# Pressure_INPUT.net
KiCad netlist of a schematic drawn in Altium Designer
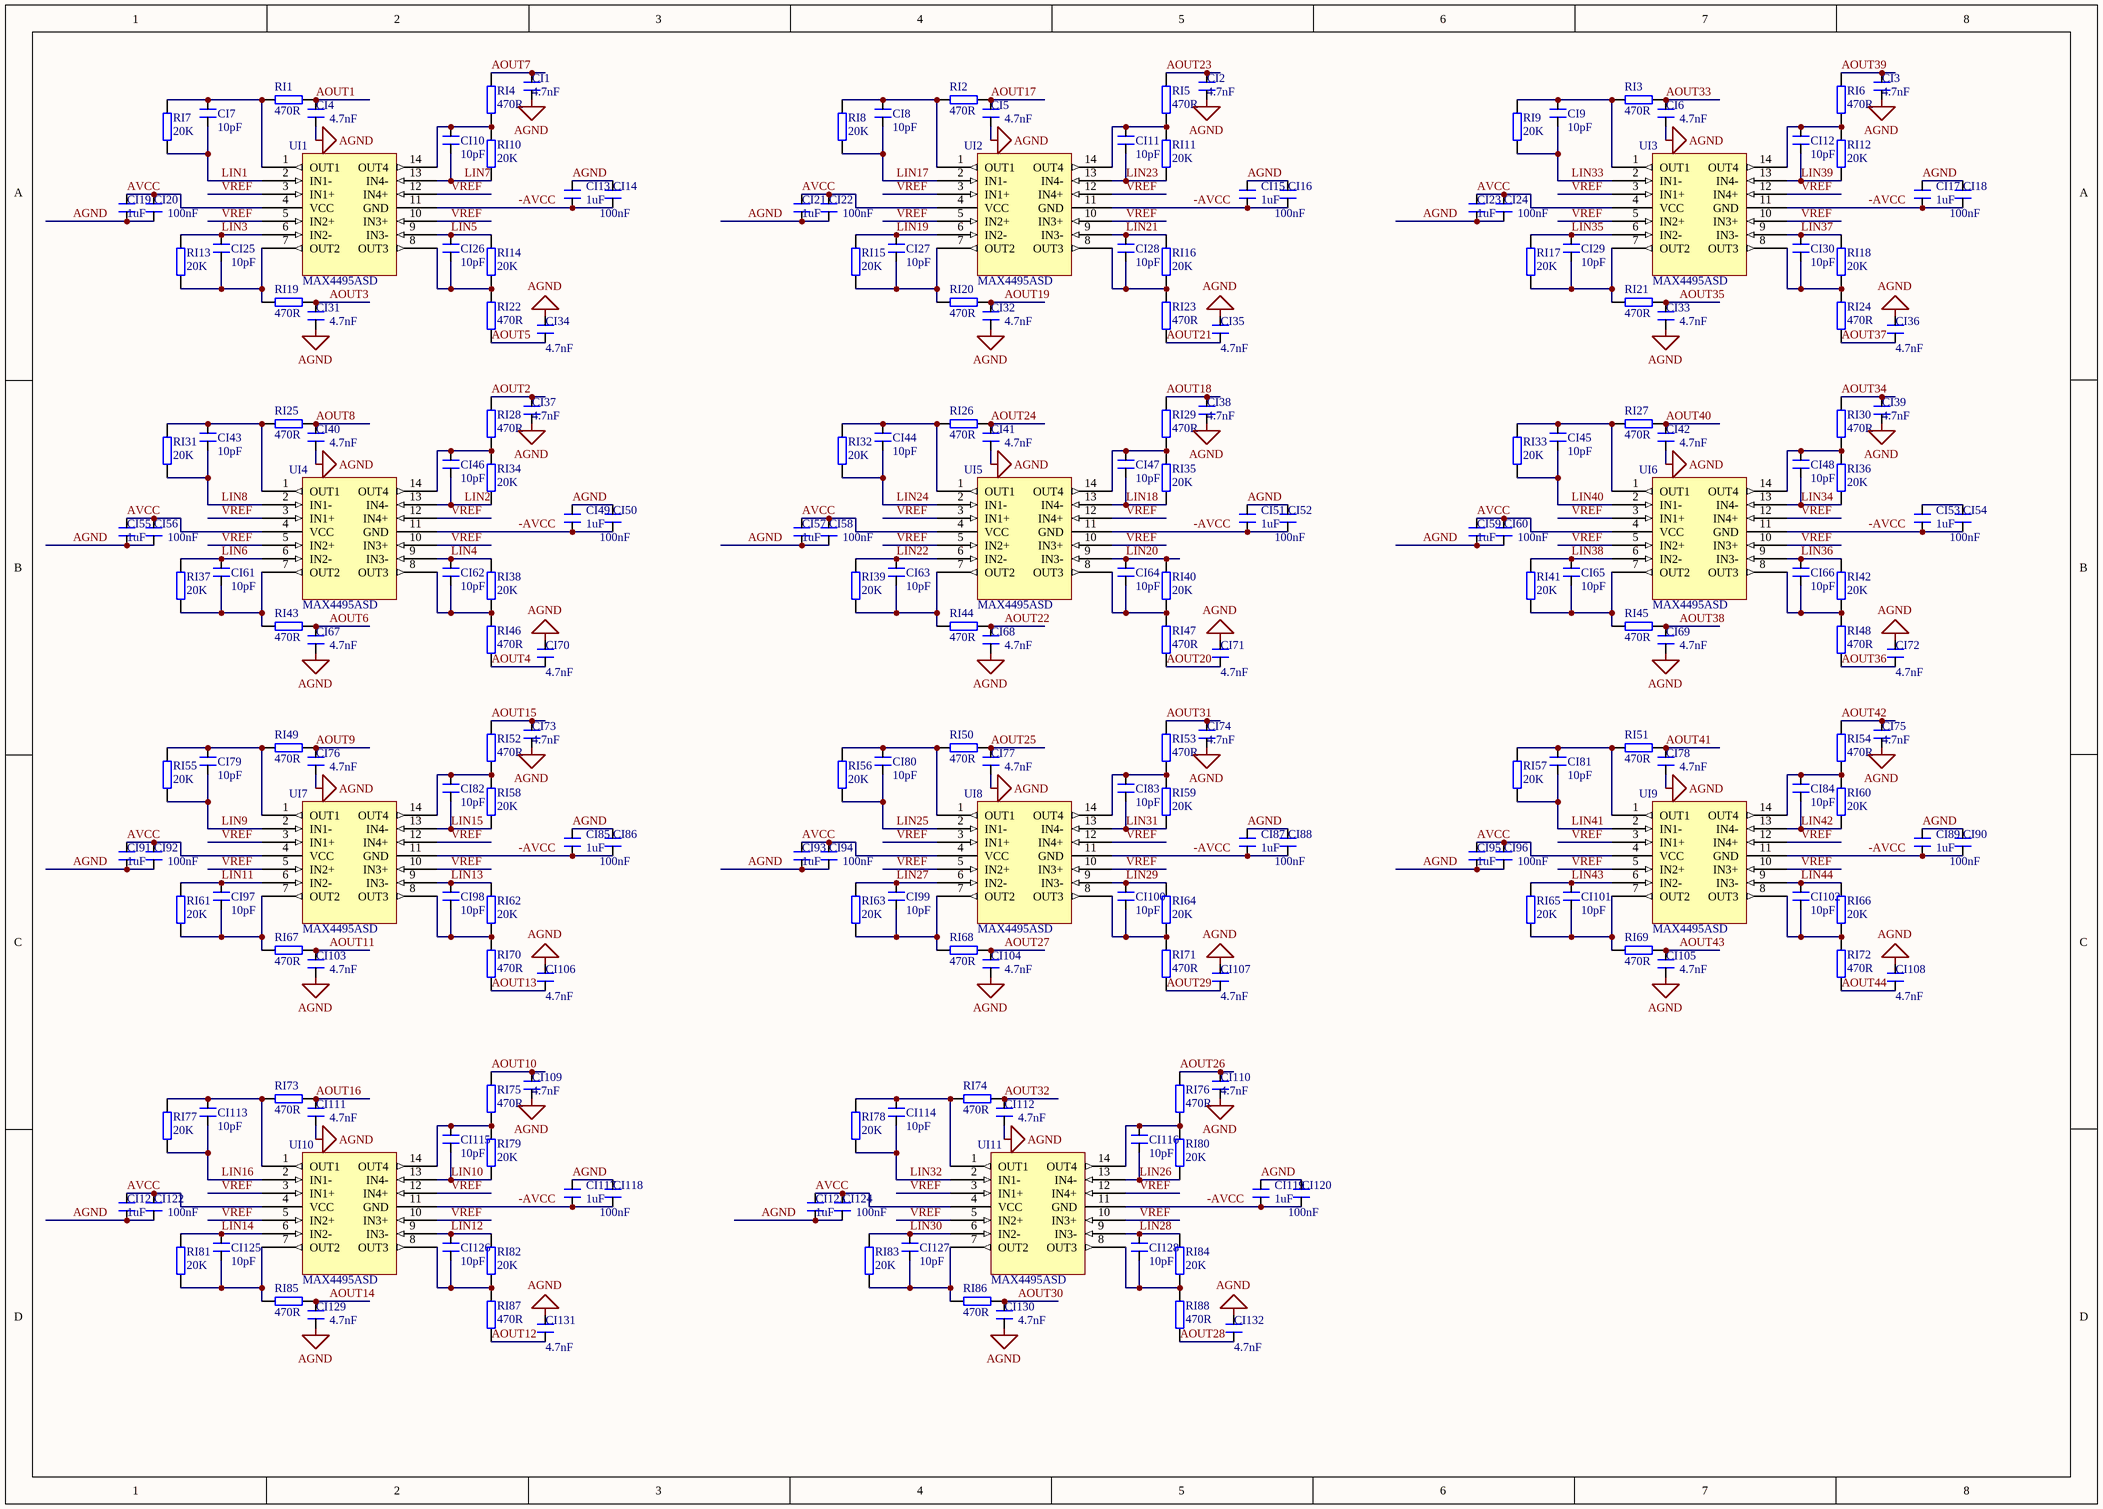
[diagram p0: Pressure_INPUT.SchDoc]

(export (version "E")
  (design (tool "Eeschema 10.0.6"))
  (components
    (comp (ref "CI1") (value "4.7nF") (footprint "C0603_HSC100") (libsource (lib "*") (part "CAP_M")))
    (comp (ref "CI2") (value "4.7nF") (footprint "C0603_HSC100") (libsource (lib "*") (part "CAP_M")))
    (comp (ref "CI3") (value "4.7nF") (footprint "C0603_HSC100") (libsource (lib "*") (part "CAP_M")))
    (comp (ref "CI4") (value "4.7nF") (footprint "C0603_HSC100") (libsource (lib "*") (part "CAP_M")))
    (comp (ref "CI5") (value "4.7nF") (footprint "C0603_HSC100") (libsource (lib "*") (part "CAP_M")))
    (comp (ref "CI6") (value "4.7nF") (footprint "C0603_HSC100") (libsource (lib "*") (part "CAP_M")))
    (comp (ref "CI7") (value "10pF") (footprint "C0603_HSC100") (libsource (lib "*") (part "CAP_M")))
    (comp (ref "CI8") (value "10pF") (footprint "C0603_HSC100") (libsource (lib "*") (part "CAP_M")))
    (comp (ref "CI9") (value "10pF") (footprint "C0603_HSC100") (libsource (lib "*") (part "CAP_M")))
    (comp (ref "CI10") (value "10pF") (footprint "C0603_HSC100") (libsource (lib "*") (part "CAP_M")))
    (comp (ref "CI11") (value "10pF") (footprint "C0603_HSC100") (libsource (lib "*") (part "CAP_M")))
    (comp (ref "CI12") (value "10pF") (footprint "C0603_HSC100") (libsource (lib "*") (part "CAP_M")))
    (comp (ref "CI13") (value "1uF") (footprint "C0603_HSC100") (libsource (lib "*") (part "CAP_M")))
    (comp (ref "CI14") (value "100nF") (footprint "C0603_HSC100") (libsource (lib "*") (part "CAP_M")))
    (comp (ref "CI15") (value "1uF") (footprint "C0603_HSC100") (libsource (lib "*") (part "CAP_M")))
    (comp (ref "CI16") (value "100nF") (footprint "C0603_HSC100") (libsource (lib "*") (part "CAP_M")))
    (comp (ref "CI17") (value "1uF") (footprint "C0603_HSC100") (libsource (lib "*") (part "CAP_M")))
    (comp (ref "CI18") (value "100nF") (footprint "C0603_HSC100") (libsource (lib "*") (part "CAP_M")))
    (comp (ref "CI19") (value "1uF") (footprint "C0603_HSC100") (libsource (lib "*") (part "CAP_M")))
    (comp (ref "CI20") (value "100nF") (footprint "C0603_HSC100") (libsource (lib "*") (part "CAP_M")))
    (comp (ref "CI21") (value "1uF") (footprint "C0603_HSC100") (libsource (lib "*") (part "CAP_M")))
    (comp (ref "CI22") (value "100nF") (footprint "C0603_HSC100") (libsource (lib "*") (part "CAP_M")))
    (comp (ref "CI23") (value "1uF") (footprint "C0603_HSC100") (libsource (lib "*") (part "CAP_M")))
    (comp (ref "CI24") (value "100nF") (footprint "C0603_HSC100") (libsource (lib "*") (part "CAP_M")))
    (comp (ref "CI25") (value "10pF") (footprint "C0603_HSC100") (libsource (lib "*") (part "CAP_M")))
    (comp (ref "CI26") (value "10pF") (footprint "C0603_HSC100") (libsource (lib "*") (part "CAP_M")))
    (comp (ref "CI27") (value "10pF") (footprint "C0603_HSC100") (libsource (lib "*") (part "CAP_M")))
    (comp (ref "CI28") (value "10pF") (footprint "C0603_HSC100") (libsource (lib "*") (part "CAP_M")))
    (comp (ref "CI29") (value "10pF") (footprint "C0603_HSC100") (libsource (lib "*") (part "CAP_M")))
    (comp (ref "CI30") (value "10pF") (footprint "C0603_HSC100") (libsource (lib "*") (part "CAP_M")))
    (comp (ref "CI31") (value "4.7nF") (footprint "C0603_HSC100") (libsource (lib "*") (part "CAP_M")))
    (comp (ref "CI32") (value "4.7nF") (footprint "C0603_HSC100") (libsource (lib "*") (part "CAP_M")))
    (comp (ref "CI33") (value "4.7nF") (footprint "C0603_HSC100") (libsource (lib "*") (part "CAP_M")))
    (comp (ref "CI34") (value "4.7nF") (footprint "C0603_HSC100") (libsource (lib "*") (part "CAP_M")))
    (comp (ref "CI35") (value "4.7nF") (footprint "C0603_HSC100") (libsource (lib "*") (part "CAP_M")))
    (comp (ref "CI36") (value "4.7nF") (footprint "C0603_HSC100") (libsource (lib "*") (part "CAP_M")))
    (comp (ref "CI37") (value "4.7nF") (footprint "C0603_HSC100") (libsource (lib "*") (part "CAP_M")))
    (comp (ref "CI38") (value "4.7nF") (footprint "C0603_HSC100") (libsource (lib "*") (part "CAP_M")))
    (comp (ref "CI39") (value "4.7nF") (footprint "C0603_HSC100") (libsource (lib "*") (part "CAP_M")))
    (comp (ref "CI40") (value "4.7nF") (footprint "C0603_HSC100") (libsource (lib "*") (part "CAP_M")))
    (comp (ref "CI41") (value "4.7nF") (footprint "C0603_HSC100") (libsource (lib "*") (part "CAP_M")))
    (comp (ref "CI42") (value "4.7nF") (footprint "C0603_HSC100") (libsource (lib "*") (part "CAP_M")))
    (comp (ref "CI43") (value "10pF") (footprint "C0603_HSC100") (libsource (lib "*") (part "CAP_M")))
    (comp (ref "CI44") (value "10pF") (footprint "C0603_HSC100") (libsource (lib "*") (part "CAP_M")))
    (comp (ref "CI45") (value "10pF") (footprint "C0603_HSC100") (libsource (lib "*") (part "CAP_M")))
    (comp (ref "CI46") (value "10pF") (footprint "C0603_HSC100") (libsource (lib "*") (part "CAP_M")))
    (comp (ref "CI47") (value "10pF") (footprint "C0603_HSC100") (libsource (lib "*") (part "CAP_M")))
    (comp (ref "CI48") (value "10pF") (footprint "C0603_HSC100") (libsource (lib "*") (part "CAP_M")))
    (comp (ref "CI49") (value "1uF") (footprint "C0603_HSC100") (libsource (lib "*") (part "CAP_M")))
    (comp (ref "CI50") (value "100nF") (footprint "C0603_HSC100") (libsource (lib "*") (part "CAP_M")))
    (comp (ref "CI51") (value "1uF") (footprint "C0603_HSC100") (libsource (lib "*") (part "CAP_M")))
    (comp (ref "CI52") (value "100nF") (footprint "C0603_HSC100") (libsource (lib "*") (part "CAP_M")))
    (comp (ref "CI53") (value "1uF") (footprint "C0603_HSC100") (libsource (lib "*") (part "CAP_M")))
    (comp (ref "CI54") (value "100nF") (footprint "C0603_HSC100") (libsource (lib "*") (part "CAP_M")))
    (comp (ref "CI55") (value "1uF") (footprint "C0603_HSC100") (libsource (lib "*") (part "CAP_M")))
    (comp (ref "CI56") (value "100nF") (footprint "C0603_HSC100") (libsource (lib "*") (part "CAP_M")))
    (comp (ref "CI57") (value "1uF") (footprint "C0603_HSC100") (libsource (lib "*") (part "CAP_M")))
    (comp (ref "CI58") (value "100nF") (footprint "C0603_HSC100") (libsource (lib "*") (part "CAP_M")))
    (comp (ref "CI59") (value "1uF") (footprint "C0603_HSC100") (libsource (lib "*") (part "CAP_M")))
    (comp (ref "CI60") (value "100nF") (footprint "C0603_HSC100") (libsource (lib "*") (part "CAP_M")))
    (comp (ref "CI61") (value "10pF") (footprint "C0603_HSC100") (libsource (lib "*") (part "CAP_M")))
    (comp (ref "CI62") (value "10pF") (footprint "C0603_HSC100") (libsource (lib "*") (part "CAP_M")))
    (comp (ref "CI63") (value "10pF") (footprint "C0603_HSC100") (libsource (lib "*") (part "CAP_M")))
    (comp (ref "CI64") (value "10pF") (footprint "C0603_HSC100") (libsource (lib "*") (part "CAP_M")))
    (comp (ref "CI65") (value "10pF") (footprint "C0603_HSC100") (libsource (lib "*") (part "CAP_M")))
    (comp (ref "CI66") (value "10pF") (footprint "C0603_HSC100") (libsource (lib "*") (part "CAP_M")))
    (comp (ref "CI67") (value "4.7nF") (footprint "C0603_HSC100") (libsource (lib "*") (part "CAP_M")))
    (comp (ref "CI68") (value "4.7nF") (footprint "C0603_HSC100") (libsource (lib "*") (part "CAP_M")))
    (comp (ref "CI69") (value "4.7nF") (footprint "C0603_HSC100") (libsource (lib "*") (part "CAP_M")))
    (comp (ref "CI70") (value "4.7nF") (footprint "C0603_HSC100") (libsource (lib "*") (part "CAP_M")))
    (comp (ref "CI71") (value "4.7nF") (footprint "C0603_HSC100") (libsource (lib "*") (part "CAP_M")))
    (comp (ref "CI72") (value "4.7nF") (footprint "C0603_HSC100") (libsource (lib "*") (part "CAP_M")))
    (comp (ref "CI73") (value "4.7nF") (footprint "C0603_HSC100") (libsource (lib "*") (part "CAP_M")))
    (comp (ref "CI74") (value "4.7nF") (footprint "C0603_HSC100") (libsource (lib "*") (part "CAP_M")))
    (comp (ref "CI75") (value "4.7nF") (footprint "C0603_HSC100") (libsource (lib "*") (part "CAP_M")))
    (comp (ref "CI76") (value "4.7nF") (footprint "C0603_HSC100") (libsource (lib "*") (part "CAP_M")))
    (comp (ref "CI77") (value "4.7nF") (footprint "C0603_HSC100") (libsource (lib "*") (part "CAP_M")))
    (comp (ref "CI78") (value "4.7nF") (footprint "C0603_HSC100") (libsource (lib "*") (part "CAP_M")))
    (comp (ref "CI79") (value "10pF") (footprint "C0603_HSC100") (libsource (lib "*") (part "CAP_M")))
    (comp (ref "CI80") (value "10pF") (footprint "C0603_HSC100") (libsource (lib "*") (part "CAP_M")))
    (comp (ref "CI81") (value "10pF") (footprint "C0603_HSC100") (libsource (lib "*") (part "CAP_M")))
    (comp (ref "CI82") (value "10pF") (footprint "C0603_HSC100") (libsource (lib "*") (part "CAP_M")))
    (comp (ref "CI83") (value "10pF") (footprint "C0603_HSC100") (libsource (lib "*") (part "CAP_M")))
    (comp (ref "CI84") (value "10pF") (footprint "C0603_HSC100") (libsource (lib "*") (part "CAP_M")))
    (comp (ref "CI85") (value "1uF") (footprint "C0603_HSC100") (libsource (lib "*") (part "CAP_M")))
    (comp (ref "CI86") (value "100nF") (footprint "C0603_HSC100") (libsource (lib "*") (part "CAP_M")))
    (comp (ref "CI87") (value "1uF") (footprint "C0603_HSC100") (libsource (lib "*") (part "CAP_M")))
    (comp (ref "CI88") (value "100nF") (footprint "C0603_HSC100") (libsource (lib "*") (part "CAP_M")))
    (comp (ref "CI89") (value "1uF") (footprint "C0603_HSC100") (libsource (lib "*") (part "CAP_M")))
    (comp (ref "CI90") (value "100nF") (footprint "C0603_HSC100") (libsource (lib "*") (part "CAP_M")))
    (comp (ref "CI91") (value "1uF") (footprint "C0603_HSC100") (libsource (lib "*") (part "CAP_M")))
    (comp (ref "CI92") (value "100nF") (footprint "C0603_HSC100") (libsource (lib "*") (part "CAP_M")))
    (comp (ref "CI93") (value "1uF") (footprint "C0603_HSC100") (libsource (lib "*") (part "CAP_M")))
    (comp (ref "CI94") (value "100nF") (footprint "C0603_HSC100") (libsource (lib "*") (part "CAP_M")))
    (comp (ref "CI95") (value "1uF") (footprint "C0603_HSC100") (libsource (lib "*") (part "CAP_M")))
    (comp (ref "CI96") (value "100nF") (footprint "C0603_HSC100") (libsource (lib "*") (part "CAP_M")))
    (comp (ref "CI97") (value "10pF") (footprint "C0603_HSC100") (libsource (lib "*") (part "CAP_M")))
    (comp (ref "CI98") (value "10pF") (footprint "C0603_HSC100") (libsource (lib "*") (part "CAP_M")))
    (comp (ref "CI99") (value "10pF") (footprint "C0603_HSC100") (libsource (lib "*") (part "CAP_M")))
    (comp (ref "CI100") (value "10pF") (footprint "C0603_HSC100") (libsource (lib "*") (part "CAP_M")))
    (comp (ref "CI101") (value "10pF") (footprint "C0603_HSC100") (libsource (lib "*") (part "CAP_M")))
    (comp (ref "CI102") (value "10pF") (footprint "C0603_HSC100") (libsource (lib "*") (part "CAP_M")))
    (comp (ref "CI103") (value "4.7nF") (footprint "C0603_HSC100") (libsource (lib "*") (part "CAP_M")))
    (comp (ref "CI104") (value "4.7nF") (footprint "C0603_HSC100") (libsource (lib "*") (part "CAP_M")))
    (comp (ref "CI105") (value "4.7nF") (footprint "C0603_HSC100") (libsource (lib "*") (part "CAP_M")))
    (comp (ref "CI106") (value "4.7nF") (footprint "C0603_HSC100") (libsource (lib "*") (part "CAP_M")))
    (comp (ref "CI107") (value "4.7nF") (footprint "C0603_HSC100") (libsource (lib "*") (part "CAP_M")))
    (comp (ref "CI108") (value "4.7nF") (footprint "C0603_HSC100") (libsource (lib "*") (part "CAP_M")))
    (comp (ref "CI109") (value "4.7nF") (footprint "C0603_HSC100") (libsource (lib "*") (part "CAP_M")))
    (comp (ref "CI110") (value "4.7nF") (footprint "C0603_HSC100") (libsource (lib "*") (part "CAP_M")))
    (comp (ref "CI111") (value "4.7nF") (footprint "C0603_HSC100") (libsource (lib "*") (part "CAP_M")))
    (comp (ref "CI112") (value "4.7nF") (footprint "C0603_HSC100") (libsource (lib "*") (part "CAP_M")))
    (comp (ref "CI113") (value "10pF") (footprint "C0603_HSC100") (libsource (lib "*") (part "CAP_M")))
    (comp (ref "CI114") (value "10pF") (footprint "C0603_HSC100") (libsource (lib "*") (part "CAP_M")))
    (comp (ref "CI115") (value "10pF") (footprint "C0603_HSC100") (libsource (lib "*") (part "CAP_M")))
    (comp (ref "CI116") (value "10pF") (footprint "C0603_HSC100") (libsource (lib "*") (part "CAP_M")))
    (comp (ref "CI117") (value "1uF") (footprint "C0603_HSC100") (libsource (lib "*") (part "CAP_M")))
    (comp (ref "CI118") (value "100nF") (footprint "C0603_HSC100") (libsource (lib "*") (part "CAP_M")))
    (comp (ref "CI119") (value "1uF") (footprint "C0603_HSC100") (libsource (lib "*") (part "CAP_M")))
    (comp (ref "CI120") (value "100nF") (footprint "C0603_HSC100") (libsource (lib "*") (part "CAP_M")))
    (comp (ref "CI121") (value "1uF") (footprint "C0603_HSC100") (libsource (lib "*") (part "CAP_M")))
    (comp (ref "CI122") (value "100nF") (footprint "C0603_HSC100") (libsource (lib "*") (part "CAP_M")))
    (comp (ref "CI123") (value "1uF") (footprint "C0603_HSC100") (libsource (lib "*") (part "CAP_M")))
    (comp (ref "CI124") (value "100nF") (footprint "C0603_HSC100") (libsource (lib "*") (part "CAP_M")))
    (comp (ref "CI125") (value "10pF") (footprint "C0603_HSC100") (libsource (lib "*") (part "CAP_M")))
    (comp (ref "CI126") (value "10pF") (footprint "C0603_HSC100") (libsource (lib "*") (part "CAP_M")))
    (comp (ref "CI127") (value "10pF") (footprint "C0603_HSC100") (libsource (lib "*") (part "CAP_M")))
    (comp (ref "CI128") (value "10pF") (footprint "C0603_HSC100") (libsource (lib "*") (part "CAP_M")))
    (comp (ref "CI129") (value "4.7nF") (footprint "C0603_HSC100") (libsource (lib "*") (part "CAP_M")))
    (comp (ref "CI130") (value "4.7nF") (footprint "C0603_HSC100") (libsource (lib "*") (part "CAP_M")))
    (comp (ref "CI131") (value "4.7nF") (footprint "C0603_HSC100") (libsource (lib "*") (part "CAP_M")))
    (comp (ref "CI132") (value "4.7nF") (footprint "C0603_HSC100") (libsource (lib "*") (part "CAP_M")))
    (comp (ref "RI1") (value "470R") (footprint "R0603_HSC100") (libsource (lib "*") (part "RES")))
    (comp (ref "RI2") (value "470R") (footprint "R0603_HSC100") (libsource (lib "*") (part "RES")))
    (comp (ref "RI3") (value "470R") (footprint "R0603_HSC100") (libsource (lib "*") (part "RES")))
    (comp (ref "RI4") (value "470R") (footprint "R0603_HSC100") (libsource (lib "*") (part "RES")))
    (comp (ref "RI5") (value "470R") (footprint "R0603_HSC100") (libsource (lib "*") (part "RES")))
    (comp (ref "RI6") (value "470R") (footprint "R0603_HSC100") (libsource (lib "*") (part "RES")))
    (comp (ref "RI7") (value "20K") (footprint "R0603_HSC100") (libsource (lib "*") (part "RES")))
    (comp (ref "RI8") (value "20K") (footprint "R0603_HSC100") (libsource (lib "*") (part "RES")))
    (comp (ref "RI9") (value "20K") (footprint "R0603_HSC100") (libsource (lib "*") (part "RES")))
    (comp (ref "RI10") (value "20K") (footprint "R0603_HSC100") (libsource (lib "*") (part "RES")))
    (comp (ref "RI11") (value "20K") (footprint "R0603_HSC100") (libsource (lib "*") (part "RES")))
    (comp (ref "RI12") (value "20K") (footprint "R0603_HSC100") (libsource (lib "*") (part "RES")))
    (comp (ref "RI13") (value "20K") (footprint "R0603_HSC100") (libsource (lib "*") (part "RES")))
    (comp (ref "RI14") (value "20K") (footprint "R0603_HSC100") (libsource (lib "*") (part "RES")))
    (comp (ref "RI15") (value "20K") (footprint "R0603_HSC100") (libsource (lib "*") (part "RES")))
    (comp (ref "RI16") (value "20K") (footprint "R0603_HSC100") (libsource (lib "*") (part "RES")))
    (comp (ref "RI17") (value "20K") (footprint "R0603_HSC100") (libsource (lib "*") (part "RES")))
    (comp (ref "RI18") (value "20K") (footprint "R0603_HSC100") (libsource (lib "*") (part "RES")))
    (comp (ref "RI19") (value "470R") (footprint "R0603_HSC100") (libsource (lib "*") (part "RES")))
    (comp (ref "RI20") (value "470R") (footprint "R0603_HSC100") (libsource (lib "*") (part "RES")))
    (comp (ref "RI21") (value "470R") (footprint "R0603_HSC100") (libsource (lib "*") (part "RES")))
    (comp (ref "RI22") (value "470R") (footprint "R0603_HSC100") (libsource (lib "*") (part "RES")))
    (comp (ref "RI23") (value "470R") (footprint "R0603_HSC100") (libsource (lib "*") (part "RES")))
    (comp (ref "RI24") (value "470R") (footprint "R0603_HSC100") (libsource (lib "*") (part "RES")))
    (comp (ref "RI25") (value "470R") (footprint "R0603_HSC100") (libsource (lib "*") (part "RES")))
    (comp (ref "RI26") (value "470R") (footprint "R0603_HSC100") (libsource (lib "*") (part "RES")))
    (comp (ref "RI27") (value "470R") (footprint "R0603_HSC100") (libsource (lib "*") (part "RES")))
    (comp (ref "RI28") (value "470R") (footprint "R0603_HSC100") (libsource (lib "*") (part "RES")))
    (comp (ref "RI29") (value "470R") (footprint "R0603_HSC100") (libsource (lib "*") (part "RES")))
    (comp (ref "RI30") (value "470R") (footprint "R0603_HSC100") (libsource (lib "*") (part "RES")))
    (comp (ref "RI31") (value "20K") (footprint "R0603_HSC100") (libsource (lib "*") (part "RES")))
    (comp (ref "RI32") (value "20K") (footprint "R0603_HSC100") (libsource (lib "*") (part "RES")))
    (comp (ref "RI33") (value "20K") (footprint "R0603_HSC100") (libsource (lib "*") (part "RES")))
    (comp (ref "RI34") (value "20K") (footprint "R0603_HSC100") (libsource (lib "*") (part "RES")))
    (comp (ref "RI35") (value "20K") (footprint "R0603_HSC100") (libsource (lib "*") (part "RES")))
    (comp (ref "RI36") (value "20K") (footprint "R0603_HSC100") (libsource (lib "*") (part "RES")))
    (comp (ref "RI37") (value "20K") (footprint "R0603_HSC100") (libsource (lib "*") (part "RES")))
    (comp (ref "RI38") (value "20K") (footprint "R0603_HSC100") (libsource (lib "*") (part "RES")))
    (comp (ref "RI39") (value "20K") (footprint "R0603_HSC100") (libsource (lib "*") (part "RES")))
    (comp (ref "RI40") (value "20K") (footprint "R0603_HSC100") (libsource (lib "*") (part "RES")))
    (comp (ref "RI41") (value "20K") (footprint "R0603_HSC100") (libsource (lib "*") (part "RES")))
    (comp (ref "RI42") (value "20K") (footprint "R0603_HSC100") (libsource (lib "*") (part "RES")))
    (comp (ref "RI43") (value "470R") (footprint "R0603_HSC100") (libsource (lib "*") (part "RES")))
    (comp (ref "RI44") (value "470R") (footprint "R0603_HSC100") (libsource (lib "*") (part "RES")))
    (comp (ref "RI45") (value "470R") (footprint "R0603_HSC100") (libsource (lib "*") (part "RES")))
    (comp (ref "RI46") (value "470R") (footprint "R0603_HSC100") (libsource (lib "*") (part "RES")))
    (comp (ref "RI47") (value "470R") (footprint "R0603_HSC100") (libsource (lib "*") (part "RES")))
    (comp (ref "RI48") (value "470R") (footprint "R0603_HSC100") (libsource (lib "*") (part "RES")))
    (comp (ref "RI49") (value "470R") (footprint "R0603_HSC100") (libsource (lib "*") (part "RES")))
    (comp (ref "RI50") (value "470R") (footprint "R0603_HSC100") (libsource (lib "*") (part "RES")))
    (comp (ref "RI51") (value "470R") (footprint "R0603_HSC100") (libsource (lib "*") (part "RES")))
    (comp (ref "RI52") (value "470R") (footprint "R0603_HSC100") (libsource (lib "*") (part "RES")))
    (comp (ref "RI53") (value "470R") (footprint "R0603_HSC100") (libsource (lib "*") (part "RES")))
    (comp (ref "RI54") (value "470R") (footprint "R0603_HSC100") (libsource (lib "*") (part "RES")))
    (comp (ref "RI55") (value "20K") (footprint "R0603_HSC100") (libsource (lib "*") (part "RES")))
    (comp (ref "RI56") (value "20K") (footprint "R0603_HSC100") (libsource (lib "*") (part "RES")))
    (comp (ref "RI57") (value "20K") (footprint "R0603_HSC100") (libsource (lib "*") (part "RES")))
    (comp (ref "RI58") (value "20K") (footprint "R0603_HSC100") (libsource (lib "*") (part "RES")))
    (comp (ref "RI59") (value "20K") (footprint "R0603_HSC100") (libsource (lib "*") (part "RES")))
    (comp (ref "RI60") (value "20K") (footprint "R0603_HSC100") (libsource (lib "*") (part "RES")))
    (comp (ref "RI61") (value "20K") (footprint "R0603_HSC100") (libsource (lib "*") (part "RES")))
    (comp (ref "RI62") (value "20K") (footprint "R0603_HSC100") (libsource (lib "*") (part "RES")))
    (comp (ref "RI63") (value "20K") (footprint "R0603_HSC100") (libsource (lib "*") (part "RES")))
    (comp (ref "RI64") (value "20K") (footprint "R0603_HSC100") (libsource (lib "*") (part "RES")))
    (comp (ref "RI65") (value "20K") (footprint "R0603_HSC100") (libsource (lib "*") (part "RES")))
    (comp (ref "RI66") (value "20K") (footprint "R0603_HSC100") (libsource (lib "*") (part "RES")))
    (comp (ref "RI67") (value "470R") (footprint "R0603_HSC100") (libsource (lib "*") (part "RES")))
    (comp (ref "RI68") (value "470R") (footprint "R0603_HSC100") (libsource (lib "*") (part "RES")))
    (comp (ref "RI69") (value "470R") (footprint "R0603_HSC100") (libsource (lib "*") (part "RES")))
    (comp (ref "RI70") (value "470R") (footprint "R0603_HSC100") (libsource (lib "*") (part "RES")))
    (comp (ref "RI71") (value "470R") (footprint "R0603_HSC100") (libsource (lib "*") (part "RES")))
    (comp (ref "RI72") (value "470R") (footprint "R0603_HSC100") (libsource (lib "*") (part "RES")))
    (comp (ref "RI73") (value "470R") (footprint "R0603_HSC100") (libsource (lib "*") (part "RES")))
    (comp (ref "RI74") (value "470R") (footprint "R0603_HSC100") (libsource (lib "*") (part "RES")))
    (comp (ref "RI75") (value "470R") (footprint "R0603_HSC100") (libsource (lib "*") (part "RES")))
    (comp (ref "RI76") (value "470R") (footprint "R0603_HSC100") (libsource (lib "*") (part "RES")))
    (comp (ref "RI77") (value "20K") (footprint "R0603_HSC100") (libsource (lib "*") (part "RES")))
    (comp (ref "RI78") (value "20K") (footprint "R0603_HSC100") (libsource (lib "*") (part "RES")))
    (comp (ref "RI79") (value "20K") (footprint "R0603_HSC100") (libsource (lib "*") (part "RES")))
    (comp (ref "RI80") (value "20K") (footprint "R0603_HSC100") (libsource (lib "*") (part "RES")))
    (comp (ref "RI81") (value "20K") (footprint "R0603_HSC100") (libsource (lib "*") (part "RES")))
    (comp (ref "RI82") (value "20K") (footprint "R0603_HSC100") (libsource (lib "*") (part "RES")))
    (comp (ref "RI83") (value "20K") (footprint "R0603_HSC100") (libsource (lib "*") (part "RES")))
    (comp (ref "RI84") (value "20K") (footprint "R0603_HSC100") (libsource (lib "*") (part "RES")))
    (comp (ref "RI85") (value "470R") (footprint "R0603_HSC100") (libsource (lib "*") (part "RES")))
    (comp (ref "RI86") (value "470R") (footprint "R0603_HSC100") (libsource (lib "*") (part "RES")))
    (comp (ref "RI87") (value "470R") (footprint "R0603_HSC100") (libsource (lib "*") (part "RES")))
    (comp (ref "RI88") (value "470R") (footprint "R0603_HSC100") (libsource (lib "*") (part "RES")))
    (comp (ref "UI1") (value "MAX4495ASD") (footprint "SO-14") (libsource (lib "MY_SCH") (part "LM324")))
    (comp (ref "UI2") (value "MAX4495ASD") (footprint "SO-14") (libsource (lib "MY_SCH") (part "LM324")))
    (comp (ref "UI3") (value "MAX4495ASD") (footprint "SO-14") (libsource (lib "MY_SCH") (part "LM324")))
    (comp (ref "UI4") (value "MAX4495ASD") (footprint "SO-14") (libsource (lib "MY_SCH") (part "LM324")))
    (comp (ref "UI5") (value "MAX4495ASD") (footprint "SO-14") (libsource (lib "MY_SCH") (part "LM324")))
    (comp (ref "UI6") (value "MAX4495ASD") (footprint "SO-14") (libsource (lib "MY_SCH") (part "LM324")))
    (comp (ref "UI7") (value "MAX4495ASD") (footprint "SO-14") (libsource (lib "MY_SCH") (part "LM324")))
    (comp (ref "UI8") (value "MAX4495ASD") (footprint "SO-14") (libsource (lib "MY_SCH") (part "LM324")))
    (comp (ref "UI9") (value "MAX4495ASD") (footprint "SO-14") (libsource (lib "MY_SCH") (part "LM324")))
    (comp (ref "UI10") (value "MAX4495ASD") (footprint "SO-14") (libsource (lib "MY_SCH") (part "LM324")))
    (comp (ref "UI11") (value "MAX4495ASD") (footprint "SO-14") (libsource (lib "MY_SCH") (part "LM324")))
  )
  (nets
    (net (code "1") (name "/-AVCC") (class "Default")
      (node (ref "CI117") (pin "2") (pintype "passive"))
      (node (ref "CI118") (pin "2") (pintype "passive"))
      (node (ref "CI119") (pin "2") (pintype "passive"))
      (node (ref "CI120") (pin "2") (pintype "passive"))
      (node (ref "CI13") (pin "2") (pintype "passive"))
      (node (ref "CI14") (pin "2") (pintype "passive"))
      (node (ref "CI15") (pin "2") (pintype "passive"))
      (node (ref "CI16") (pin "2") (pintype "passive"))
      (node (ref "CI17") (pin "2") (pintype "passive"))
      (node (ref "CI18") (pin "2") (pintype "passive"))
      (node (ref "CI49") (pin "2") (pintype "passive"))
      (node (ref "CI50") (pin "2") (pintype "passive"))
      (node (ref "CI51") (pin "2") (pintype "passive"))
      (node (ref "CI52") (pin "2") (pintype "passive"))
      (node (ref "CI53") (pin "2") (pintype "passive"))
      (node (ref "CI54") (pin "2") (pintype "passive"))
      (node (ref "CI85") (pin "2") (pintype "passive"))
      (node (ref "CI86") (pin "2") (pintype "passive"))
      (node (ref "CI87") (pin "2") (pintype "passive"))
      (node (ref "CI88") (pin "2") (pintype "passive"))
      (node (ref "CI89") (pin "2") (pintype "passive"))
      (node (ref "CI90") (pin "2") (pintype "passive"))
      (node (ref "UI1") (pin "11") (pinfunction "GND_11") (pintype "power_in"))
      (node (ref "UI10") (pin "11") (pinfunction "GND_11") (pintype "power_in"))
      (node (ref "UI11") (pin "11") (pinfunction "GND_11") (pintype "power_in"))
      (node (ref "UI2") (pin "11") (pinfunction "GND_11") (pintype "power_in"))
      (node (ref "UI3") (pin "11") (pinfunction "GND_11") (pintype "power_in"))
      (node (ref "UI4") (pin "11") (pinfunction "GND_11") (pintype "power_in"))
      (node (ref "UI5") (pin "11") (pinfunction "GND_11") (pintype "power_in"))
      (node (ref "UI6") (pin "11") (pinfunction "GND_11") (pintype "power_in"))
      (node (ref "UI7") (pin "11") (pinfunction "GND_11") (pintype "power_in"))
      (node (ref "UI8") (pin "11") (pinfunction "GND_11") (pintype "power_in"))
      (node (ref "UI9") (pin "11") (pinfunction "GND_11") (pintype "power_in"))
    )
    (net (code "2") (name "/AOUT1") (class "Default")
      (node (ref "CI4") (pin "1") (pintype "passive"))
      (node (ref "RI1") (pin "1") (pintype "passive"))
    )
    (net (code "3") (name "/AOUT2") (class "Default")
      (node (ref "CI37") (pin "1") (pintype "passive"))
      (node (ref "RI28") (pin "2") (pintype "passive"))
    )
    (net (code "4") (name "/AOUT3") (class "Default")
      (node (ref "CI31") (pin "1") (pintype "passive"))
      (node (ref "RI19") (pin "1") (pintype "passive"))
    )
    (net (code "5") (name "/AOUT4") (class "Default")
      (node (ref "CI70") (pin "2") (pintype "passive"))
      (node (ref "RI46") (pin "2") (pintype "passive"))
    )
    (net (code "6") (name "/AOUT5") (class "Default")
      (node (ref "CI34") (pin "2") (pintype "passive"))
      (node (ref "RI22") (pin "2") (pintype "passive"))
    )
    (net (code "7") (name "/AOUT6") (class "Default")
      (node (ref "CI67") (pin "1") (pintype "passive"))
      (node (ref "RI43") (pin "1") (pintype "passive"))
    )
    (net (code "8") (name "/AOUT7") (class "Default")
      (node (ref "CI1") (pin "1") (pintype "passive"))
      (node (ref "RI4") (pin "2") (pintype "passive"))
    )
    (net (code "9") (name "/AOUT8") (class "Default")
      (node (ref "CI40") (pin "1") (pintype "passive"))
      (node (ref "RI25") (pin "1") (pintype "passive"))
    )
    (net (code "10") (name "/AOUT9") (class "Default")
      (node (ref "CI76") (pin "1") (pintype "passive"))
      (node (ref "RI49") (pin "1") (pintype "passive"))
    )
    (net (code "11") (name "/AOUT10") (class "Default")
      (node (ref "CI109") (pin "1") (pintype "passive"))
      (node (ref "RI75") (pin "2") (pintype "passive"))
    )
    (net (code "12") (name "/AOUT11") (class "Default")
      (node (ref "CI103") (pin "1") (pintype "passive"))
      (node (ref "RI67") (pin "1") (pintype "passive"))
    )
    (net (code "13") (name "/AOUT12") (class "Default")
      (node (ref "CI131") (pin "2") (pintype "passive"))
      (node (ref "RI87") (pin "2") (pintype "passive"))
    )
    (net (code "14") (name "/AOUT13") (class "Default")
      (node (ref "CI106") (pin "2") (pintype "passive"))
      (node (ref "RI70") (pin "2") (pintype "passive"))
    )
    (net (code "15") (name "/AOUT14") (class "Default")
      (node (ref "CI129") (pin "1") (pintype "passive"))
      (node (ref "RI85") (pin "1") (pintype "passive"))
    )
    (net (code "16") (name "/AOUT15") (class "Default")
      (node (ref "CI73") (pin "1") (pintype "passive"))
      (node (ref "RI52") (pin "2") (pintype "passive"))
    )
    (net (code "17") (name "/AOUT16") (class "Default")
      (node (ref "CI111") (pin "1") (pintype "passive"))
      (node (ref "RI73") (pin "1") (pintype "passive"))
    )
    (net (code "18") (name "/AOUT17") (class "Default")
      (node (ref "CI5") (pin "1") (pintype "passive"))
      (node (ref "RI2") (pin "1") (pintype "passive"))
    )
    (net (code "19") (name "/AOUT18") (class "Default")
      (node (ref "CI38") (pin "1") (pintype "passive"))
      (node (ref "RI29") (pin "2") (pintype "passive"))
    )
    (net (code "20") (name "/AOUT19") (class "Default")
      (node (ref "CI32") (pin "1") (pintype "passive"))
      (node (ref "RI20") (pin "1") (pintype "passive"))
    )
    (net (code "21") (name "/AOUT20") (class "Default")
      (node (ref "CI71") (pin "2") (pintype "passive"))
      (node (ref "RI47") (pin "2") (pintype "passive"))
    )
    (net (code "22") (name "/AOUT21") (class "Default")
      (node (ref "CI35") (pin "2") (pintype "passive"))
      (node (ref "RI23") (pin "2") (pintype "passive"))
    )
    (net (code "23") (name "/AOUT22") (class "Default")
      (node (ref "CI68") (pin "1") (pintype "passive"))
      (node (ref "RI44") (pin "1") (pintype "passive"))
    )
    (net (code "24") (name "/AOUT23") (class "Default")
      (node (ref "CI2") (pin "1") (pintype "passive"))
      (node (ref "RI5") (pin "2") (pintype "passive"))
    )
    (net (code "25") (name "/AOUT24") (class "Default")
      (node (ref "CI41") (pin "1") (pintype "passive"))
      (node (ref "RI26") (pin "1") (pintype "passive"))
    )
    (net (code "26") (name "/AOUT25") (class "Default")
      (node (ref "CI77") (pin "1") (pintype "passive"))
      (node (ref "RI50") (pin "1") (pintype "passive"))
    )
    (net (code "27") (name "/AOUT26") (class "Default")
      (node (ref "CI110") (pin "1") (pintype "passive"))
      (node (ref "RI76") (pin "2") (pintype "passive"))
    )
    (net (code "28") (name "/AOUT27") (class "Default")
      (node (ref "CI104") (pin "1") (pintype "passive"))
      (node (ref "RI68") (pin "1") (pintype "passive"))
    )
    (net (code "29") (name "/AOUT28") (class "Default")
      (node (ref "CI132") (pin "2") (pintype "passive"))
      (node (ref "RI88") (pin "2") (pintype "passive"))
    )
    (net (code "30") (name "/AOUT29") (class "Default")
      (node (ref "CI107") (pin "2") (pintype "passive"))
      (node (ref "RI71") (pin "2") (pintype "passive"))
    )
    (net (code "31") (name "/AOUT30") (class "Default")
      (node (ref "CI130") (pin "1") (pintype "passive"))
      (node (ref "RI86") (pin "1") (pintype "passive"))
    )
    (net (code "32") (name "/AOUT31") (class "Default")
      (node (ref "CI74") (pin "1") (pintype "passive"))
      (node (ref "RI53") (pin "2") (pintype "passive"))
    )
    (net (code "33") (name "/AOUT32") (class "Default")
      (node (ref "CI112") (pin "1") (pintype "passive"))
      (node (ref "RI74") (pin "1") (pintype "passive"))
    )
    (net (code "34") (name "/AOUT33") (class "Default")
      (node (ref "CI6") (pin "1") (pintype "passive"))
      (node (ref "RI3") (pin "1") (pintype "passive"))
    )
    (net (code "35") (name "/AOUT34") (class "Default")
      (node (ref "CI39") (pin "1") (pintype "passive"))
      (node (ref "RI30") (pin "2") (pintype "passive"))
    )
    (net (code "36") (name "/AOUT35") (class "Default")
      (node (ref "CI33") (pin "1") (pintype "passive"))
      (node (ref "RI21") (pin "1") (pintype "passive"))
    )
    (net (code "37") (name "/AOUT36") (class "Default")
      (node (ref "CI72") (pin "2") (pintype "passive"))
      (node (ref "RI48") (pin "2") (pintype "passive"))
    )
    (net (code "38") (name "/AOUT37") (class "Default")
      (node (ref "CI36") (pin "2") (pintype "passive"))
      (node (ref "RI24") (pin "2") (pintype "passive"))
    )
    (net (code "39") (name "/AOUT38") (class "Default")
      (node (ref "CI69") (pin "1") (pintype "passive"))
      (node (ref "RI45") (pin "1") (pintype "passive"))
    )
    (net (code "40") (name "/AOUT39") (class "Default")
      (node (ref "CI3") (pin "1") (pintype "passive"))
      (node (ref "RI6") (pin "2") (pintype "passive"))
    )
    (net (code "41") (name "/AOUT40") (class "Default")
      (node (ref "CI42") (pin "1") (pintype "passive"))
      (node (ref "RI27") (pin "1") (pintype "passive"))
    )
    (net (code "42") (name "/AOUT41") (class "Default")
      (node (ref "CI78") (pin "1") (pintype "passive"))
      (node (ref "RI51") (pin "1") (pintype "passive"))
    )
    (net (code "43") (name "/AOUT42") (class "Default")
      (node (ref "CI75") (pin "1") (pintype "passive"))
      (node (ref "RI54") (pin "2") (pintype "passive"))
    )
    (net (code "44") (name "/AOUT43") (class "Default")
      (node (ref "CI105") (pin "1") (pintype "passive"))
      (node (ref "RI69") (pin "1") (pintype "passive"))
    )
    (net (code "45") (name "/AOUT44") (class "Default")
      (node (ref "CI108") (pin "2") (pintype "passive"))
      (node (ref "RI72") (pin "2") (pintype "passive"))
    )
    (net (code "46") (name "/AVCC") (class "Default")
      (node (ref "CI121") (pin "1") (pintype "passive"))
      (node (ref "CI122") (pin "1") (pintype "passive"))
      (node (ref "CI123") (pin "1") (pintype "passive"))
      (node (ref "CI124") (pin "1") (pintype "passive"))
      (node (ref "CI19") (pin "1") (pintype "passive"))
      (node (ref "CI20") (pin "1") (pintype "passive"))
      (node (ref "CI21") (pin "1") (pintype "passive"))
      (node (ref "CI22") (pin "1") (pintype "passive"))
      (node (ref "CI23") (pin "1") (pintype "passive"))
      (node (ref "CI24") (pin "1") (pintype "passive"))
      (node (ref "CI55") (pin "1") (pintype "passive"))
      (node (ref "CI56") (pin "1") (pintype "passive"))
      (node (ref "CI57") (pin "1") (pintype "passive"))
      (node (ref "CI58") (pin "1") (pintype "passive"))
      (node (ref "CI59") (pin "1") (pintype "passive"))
      (node (ref "CI60") (pin "1") (pintype "passive"))
      (node (ref "CI91") (pin "1") (pintype "passive"))
      (node (ref "CI92") (pin "1") (pintype "passive"))
      (node (ref "CI93") (pin "1") (pintype "passive"))
      (node (ref "CI94") (pin "1") (pintype "passive"))
      (node (ref "CI95") (pin "1") (pintype "passive"))
      (node (ref "CI96") (pin "1") (pintype "passive"))
      (node (ref "UI1") (pin "4") (pinfunction "VCC_4") (pintype "power_in"))
      (node (ref "UI10") (pin "4") (pinfunction "VCC_4") (pintype "power_in"))
      (node (ref "UI11") (pin "4") (pinfunction "VCC_4") (pintype "power_in"))
      (node (ref "UI2") (pin "4") (pinfunction "VCC_4") (pintype "power_in"))
      (node (ref "UI3") (pin "4") (pinfunction "VCC_4") (pintype "power_in"))
      (node (ref "UI4") (pin "4") (pinfunction "VCC_4") (pintype "power_in"))
      (node (ref "UI5") (pin "4") (pinfunction "VCC_4") (pintype "power_in"))
      (node (ref "UI6") (pin "4") (pinfunction "VCC_4") (pintype "power_in"))
      (node (ref "UI7") (pin "4") (pinfunction "VCC_4") (pintype "power_in"))
      (node (ref "UI8") (pin "4") (pinfunction "VCC_4") (pintype "power_in"))
      (node (ref "UI9") (pin "4") (pinfunction "VCC_4") (pintype "power_in"))
    )
    (net (code "47") (name "/LIN1") (class "Default")
      (node (ref "CI7") (pin "2") (pintype "passive"))
      (node (ref "RI7") (pin "1") (pintype "passive"))
      (node (ref "UI1") (pin "2") (pinfunction "IN1-_2") (pintype "input"))
    )
    (net (code "48") (name "/LIN2") (class "Default")
      (node (ref "CI46") (pin "2") (pintype "passive"))
      (node (ref "RI34") (pin "1") (pintype "passive"))
      (node (ref "UI4") (pin "13") (pinfunction "IN4-_13") (pintype "input"))
    )
    (net (code "49") (name "/LIN3") (class "Default")
      (node (ref "CI25") (pin "1") (pintype "passive"))
      (node (ref "RI13") (pin "1") (pintype "passive"))
      (node (ref "UI1") (pin "6") (pinfunction "IN2-_6") (pintype "input"))
    )
    (net (code "50") (name "/LIN4") (class "Default")
      (node (ref "CI62") (pin "1") (pintype "passive"))
      (node (ref "RI38") (pin "2") (pintype "passive"))
      (node (ref "UI4") (pin "9") (pinfunction "IN3-_9") (pintype "input"))
    )
    (net (code "51") (name "/LIN5") (class "Default")
      (node (ref "CI26") (pin "1") (pintype "passive"))
      (node (ref "RI14") (pin "2") (pintype "passive"))
      (node (ref "UI1") (pin "9") (pinfunction "IN3-_9") (pintype "input"))
    )
    (net (code "52") (name "/LIN6") (class "Default")
      (node (ref "CI61") (pin "1") (pintype "passive"))
      (node (ref "RI37") (pin "1") (pintype "passive"))
      (node (ref "UI4") (pin "6") (pinfunction "IN2-_6") (pintype "input"))
    )
    (net (code "53") (name "/LIN7") (class "Default")
      (node (ref "CI10") (pin "2") (pintype "passive"))
      (node (ref "RI10") (pin "1") (pintype "passive"))
      (node (ref "UI1") (pin "13") (pinfunction "IN4-_13") (pintype "input"))
    )
    (net (code "54") (name "/LIN8") (class "Default")
      (node (ref "CI43") (pin "2") (pintype "passive"))
      (node (ref "RI31") (pin "1") (pintype "passive"))
      (node (ref "UI4") (pin "2") (pinfunction "IN1-_2") (pintype "input"))
    )
    (net (code "55") (name "/LIN9") (class "Default")
      (node (ref "CI79") (pin "2") (pintype "passive"))
      (node (ref "RI55") (pin "1") (pintype "passive"))
      (node (ref "UI7") (pin "2") (pinfunction "IN1-_2") (pintype "input"))
    )
    (net (code "56") (name "/LIN10") (class "Default")
      (node (ref "CI115") (pin "2") (pintype "passive"))
      (node (ref "RI79") (pin "1") (pintype "passive"))
      (node (ref "UI10") (pin "13") (pinfunction "IN4-_13") (pintype "input"))
    )
    (net (code "57") (name "/LIN11") (class "Default")
      (node (ref "CI97") (pin "1") (pintype "passive"))
      (node (ref "RI61") (pin "1") (pintype "passive"))
      (node (ref "UI7") (pin "6") (pinfunction "IN2-_6") (pintype "input"))
    )
    (net (code "58") (name "/LIN12") (class "Default")
      (node (ref "CI126") (pin "1") (pintype "passive"))
      (node (ref "RI82") (pin "2") (pintype "passive"))
      (node (ref "UI10") (pin "9") (pinfunction "IN3-_9") (pintype "input"))
    )
    (net (code "59") (name "/LIN13") (class "Default")
      (node (ref "CI98") (pin "1") (pintype "passive"))
      (node (ref "RI62") (pin "2") (pintype "passive"))
      (node (ref "UI7") (pin "9") (pinfunction "IN3-_9") (pintype "input"))
    )
    (net (code "60") (name "/LIN14") (class "Default")
      (node (ref "CI125") (pin "1") (pintype "passive"))
      (node (ref "RI81") (pin "1") (pintype "passive"))
      (node (ref "UI10") (pin "6") (pinfunction "IN2-_6") (pintype "input"))
    )
    (net (code "61") (name "/LIN15") (class "Default")
      (node (ref "CI82") (pin "2") (pintype "passive"))
      (node (ref "RI58") (pin "1") (pintype "passive"))
      (node (ref "UI7") (pin "13") (pinfunction "IN4-_13") (pintype "input"))
    )
    (net (code "62") (name "/LIN16") (class "Default")
      (node (ref "CI113") (pin "2") (pintype "passive"))
      (node (ref "RI77") (pin "1") (pintype "passive"))
      (node (ref "UI10") (pin "2") (pinfunction "IN1-_2") (pintype "input"))
    )
    (net (code "63") (name "/LIN17") (class "Default")
      (node (ref "CI8") (pin "2") (pintype "passive"))
      (node (ref "RI8") (pin "1") (pintype "passive"))
      (node (ref "UI2") (pin "2") (pinfunction "IN1-_2") (pintype "input"))
    )
    (net (code "64") (name "/LIN18") (class "Default")
      (node (ref "CI47") (pin "2") (pintype "passive"))
      (node (ref "RI35") (pin "1") (pintype "passive"))
      (node (ref "UI5") (pin "13") (pinfunction "IN4-_13") (pintype "input"))
    )
    (net (code "65") (name "/LIN19") (class "Default")
      (node (ref "CI27") (pin "1") (pintype "passive"))
      (node (ref "RI15") (pin "1") (pintype "passive"))
      (node (ref "UI2") (pin "6") (pinfunction "IN2-_6") (pintype "input"))
    )
    (net (code "66") (name "/LIN20") (class "Default")
      (node (ref "CI64") (pin "1") (pintype "passive"))
      (node (ref "RI40") (pin "2") (pintype "passive"))
      (node (ref "UI5") (pin "9") (pinfunction "IN3-_9") (pintype "input"))
    )
    (net (code "67") (name "/LIN21") (class "Default")
      (node (ref "CI28") (pin "1") (pintype "passive"))
      (node (ref "RI16") (pin "2") (pintype "passive"))
      (node (ref "UI2") (pin "9") (pinfunction "IN3-_9") (pintype "input"))
    )
    (net (code "68") (name "/LIN22") (class "Default")
      (node (ref "CI63") (pin "1") (pintype "passive"))
      (node (ref "RI39") (pin "1") (pintype "passive"))
      (node (ref "UI5") (pin "6") (pinfunction "IN2-_6") (pintype "input"))
    )
    (net (code "69") (name "/LIN23") (class "Default")
      (node (ref "CI11") (pin "2") (pintype "passive"))
      (node (ref "RI11") (pin "1") (pintype "passive"))
      (node (ref "UI2") (pin "13") (pinfunction "IN4-_13") (pintype "input"))
    )
    (net (code "70") (name "/LIN24") (class "Default")
      (node (ref "CI44") (pin "2") (pintype "passive"))
      (node (ref "RI32") (pin "1") (pintype "passive"))
      (node (ref "UI5") (pin "2") (pinfunction "IN1-_2") (pintype "input"))
    )
    (net (code "71") (name "/LIN25") (class "Default")
      (node (ref "CI80") (pin "2") (pintype "passive"))
      (node (ref "RI56") (pin "1") (pintype "passive"))
      (node (ref "UI8") (pin "2") (pinfunction "IN1-_2") (pintype "input"))
    )
    (net (code "72") (name "/LIN26") (class "Default")
      (node (ref "CI116") (pin "2") (pintype "passive"))
      (node (ref "RI80") (pin "1") (pintype "passive"))
      (node (ref "UI11") (pin "13") (pinfunction "IN4-_13") (pintype "input"))
    )
    (net (code "73") (name "/LIN27") (class "Default")
      (node (ref "CI99") (pin "1") (pintype "passive"))
      (node (ref "RI63") (pin "1") (pintype "passive"))
      (node (ref "UI8") (pin "6") (pinfunction "IN2-_6") (pintype "input"))
    )
    (net (code "74") (name "/LIN28") (class "Default")
      (node (ref "CI128") (pin "1") (pintype "passive"))
      (node (ref "RI84") (pin "2") (pintype "passive"))
      (node (ref "UI11") (pin "9") (pinfunction "IN3-_9") (pintype "input"))
    )
    (net (code "75") (name "/LIN29") (class "Default")
      (node (ref "CI100") (pin "1") (pintype "passive"))
      (node (ref "RI64") (pin "2") (pintype "passive"))
      (node (ref "UI8") (pin "9") (pinfunction "IN3-_9") (pintype "input"))
    )
    (net (code "76") (name "/LIN30") (class "Default")
      (node (ref "CI127") (pin "1") (pintype "passive"))
      (node (ref "RI83") (pin "1") (pintype "passive"))
      (node (ref "UI11") (pin "6") (pinfunction "IN2-_6") (pintype "input"))
    )
    (net (code "77") (name "/LIN31") (class "Default")
      (node (ref "CI83") (pin "2") (pintype "passive"))
      (node (ref "RI59") (pin "1") (pintype "passive"))
      (node (ref "UI8") (pin "13") (pinfunction "IN4-_13") (pintype "input"))
    )
    (net (code "78") (name "/LIN32") (class "Default")
      (node (ref "CI114") (pin "2") (pintype "passive"))
      (node (ref "RI78") (pin "1") (pintype "passive"))
      (node (ref "UI11") (pin "2") (pinfunction "IN1-_2") (pintype "input"))
    )
    (net (code "79") (name "/LIN33") (class "Default")
      (node (ref "CI9") (pin "2") (pintype "passive"))
      (node (ref "RI9") (pin "1") (pintype "passive"))
      (node (ref "UI3") (pin "2") (pinfunction "IN1-_2") (pintype "input"))
    )
    (net (code "80") (name "/LIN34") (class "Default")
      (node (ref "CI48") (pin "2") (pintype "passive"))
      (node (ref "RI36") (pin "1") (pintype "passive"))
      (node (ref "UI6") (pin "13") (pinfunction "IN4-_13") (pintype "input"))
    )
    (net (code "81") (name "/LIN35") (class "Default")
      (node (ref "CI29") (pin "1") (pintype "passive"))
      (node (ref "RI17") (pin "1") (pintype "passive"))
      (node (ref "UI3") (pin "6") (pinfunction "IN2-_6") (pintype "input"))
    )
    (net (code "82") (name "/LIN36") (class "Default")
      (node (ref "CI66") (pin "1") (pintype "passive"))
      (node (ref "RI42") (pin "2") (pintype "passive"))
      (node (ref "UI6") (pin "9") (pinfunction "IN3-_9") (pintype "input"))
    )
    (net (code "83") (name "/LIN37") (class "Default")
      (node (ref "CI30") (pin "1") (pintype "passive"))
      (node (ref "RI18") (pin "2") (pintype "passive"))
      (node (ref "UI3") (pin "9") (pinfunction "IN3-_9") (pintype "input"))
    )
    (net (code "84") (name "/LIN38") (class "Default")
      (node (ref "CI65") (pin "1") (pintype "passive"))
      (node (ref "RI41") (pin "1") (pintype "passive"))
      (node (ref "UI6") (pin "6") (pinfunction "IN2-_6") (pintype "input"))
    )
    (net (code "85") (name "/LIN39") (class "Default")
      (node (ref "CI12") (pin "2") (pintype "passive"))
      (node (ref "RI12") (pin "1") (pintype "passive"))
      (node (ref "UI3") (pin "13") (pinfunction "IN4-_13") (pintype "input"))
    )
    (net (code "86") (name "/LIN40") (class "Default")
      (node (ref "CI45") (pin "2") (pintype "passive"))
      (node (ref "RI33") (pin "1") (pintype "passive"))
      (node (ref "UI6") (pin "2") (pinfunction "IN1-_2") (pintype "input"))
    )
    (net (code "87") (name "/LIN41") (class "Default")
      (node (ref "CI81") (pin "2") (pintype "passive"))
      (node (ref "RI57") (pin "1") (pintype "passive"))
      (node (ref "UI9") (pin "2") (pinfunction "IN1-_2") (pintype "input"))
    )
    (net (code "88") (name "/LIN42") (class "Default")
      (node (ref "CI84") (pin "2") (pintype "passive"))
      (node (ref "RI60") (pin "1") (pintype "passive"))
      (node (ref "UI9") (pin "13") (pinfunction "IN4-_13") (pintype "input"))
    )
    (net (code "89") (name "/LIN43") (class "Default")
      (node (ref "CI101") (pin "1") (pintype "passive"))
      (node (ref "RI65") (pin "1") (pintype "passive"))
      (node (ref "UI9") (pin "6") (pinfunction "IN2-_6") (pintype "input"))
    )
    (net (code "90") (name "/LIN44") (class "Default")
      (node (ref "CI102") (pin "1") (pintype "passive"))
      (node (ref "RI66") (pin "2") (pintype "passive"))
      (node (ref "UI9") (pin "9") (pinfunction "IN3-_9") (pintype "input"))
    )
    (net (code "91") (name "/VREF") (class "Default")
      (node (ref "UI1") (pin "10") (pinfunction "IN3+_10") (pintype "input"))
      (node (ref "UI1") (pin "12") (pinfunction "IN4+_12") (pintype "input"))
      (node (ref "UI1") (pin "3") (pinfunction "IN1+_3") (pintype "input"))
      (node (ref "UI1") (pin "5") (pinfunction "IN2+_5") (pintype "input"))
      (node (ref "UI10") (pin "10") (pinfunction "IN3+_10") (pintype "input"))
      (node (ref "UI10") (pin "12") (pinfunction "IN4+_12") (pintype "input"))
      (node (ref "UI10") (pin "3") (pinfunction "IN1+_3") (pintype "input"))
      (node (ref "UI10") (pin "5") (pinfunction "IN2+_5") (pintype "input"))
      (node (ref "UI11") (pin "10") (pinfunction "IN3+_10") (pintype "input"))
      (node (ref "UI11") (pin "12") (pinfunction "IN4+_12") (pintype "input"))
      (node (ref "UI11") (pin "3") (pinfunction "IN1+_3") (pintype "input"))
      (node (ref "UI11") (pin "5") (pinfunction "IN2+_5") (pintype "input"))
      (node (ref "UI2") (pin "10") (pinfunction "IN3+_10") (pintype "input"))
      (node (ref "UI2") (pin "12") (pinfunction "IN4+_12") (pintype "input"))
      (node (ref "UI2") (pin "3") (pinfunction "IN1+_3") (pintype "input"))
      (node (ref "UI2") (pin "5") (pinfunction "IN2+_5") (pintype "input"))
      (node (ref "UI3") (pin "10") (pinfunction "IN3+_10") (pintype "input"))
      (node (ref "UI3") (pin "12") (pinfunction "IN4+_12") (pintype "input"))
      (node (ref "UI3") (pin "3") (pinfunction "IN1+_3") (pintype "input"))
      (node (ref "UI3") (pin "5") (pinfunction "IN2+_5") (pintype "input"))
      (node (ref "UI4") (pin "10") (pinfunction "IN3+_10") (pintype "input"))
      (node (ref "UI4") (pin "12") (pinfunction "IN4+_12") (pintype "input"))
      (node (ref "UI4") (pin "3") (pinfunction "IN1+_3") (pintype "input"))
      (node (ref "UI4") (pin "5") (pinfunction "IN2+_5") (pintype "input"))
      (node (ref "UI5") (pin "10") (pinfunction "IN3+_10") (pintype "input"))
      (node (ref "UI5") (pin "12") (pinfunction "IN4+_12") (pintype "input"))
      (node (ref "UI5") (pin "3") (pinfunction "IN1+_3") (pintype "input"))
      (node (ref "UI5") (pin "5") (pinfunction "IN2+_5") (pintype "input"))
      (node (ref "UI6") (pin "10") (pinfunction "IN3+_10") (pintype "input"))
      (node (ref "UI6") (pin "12") (pinfunction "IN4+_12") (pintype "input"))
      (node (ref "UI6") (pin "3") (pinfunction "IN1+_3") (pintype "input"))
      (node (ref "UI6") (pin "5") (pinfunction "IN2+_5") (pintype "input"))
      (node (ref "UI7") (pin "10") (pinfunction "IN3+_10") (pintype "input"))
      (node (ref "UI7") (pin "12") (pinfunction "IN4+_12") (pintype "input"))
      (node (ref "UI7") (pin "3") (pinfunction "IN1+_3") (pintype "input"))
      (node (ref "UI7") (pin "5") (pinfunction "IN2+_5") (pintype "input"))
      (node (ref "UI8") (pin "10") (pinfunction "IN3+_10") (pintype "input"))
      (node (ref "UI8") (pin "12") (pinfunction "IN4+_12") (pintype "input"))
      (node (ref "UI8") (pin "3") (pinfunction "IN1+_3") (pintype "input"))
      (node (ref "UI8") (pin "5") (pinfunction "IN2+_5") (pintype "input"))
      (node (ref "UI9") (pin "10") (pinfunction "IN3+_10") (pintype "input"))
      (node (ref "UI9") (pin "12") (pinfunction "IN4+_12") (pintype "input"))
      (node (ref "UI9") (pin "3") (pinfunction "IN1+_3") (pintype "input"))
      (node (ref "UI9") (pin "5") (pinfunction "IN2+_5") (pintype "input"))
    )
    (net (code "92") (name "AGND") (class "Default")
      (node (ref "CI1") (pin "2") (pintype "passive"))
      (node (ref "CI103") (pin "2") (pintype "passive"))
      (node (ref "CI104") (pin "2") (pintype "passive"))
      (node (ref "CI105") (pin "2") (pintype "passive"))
      (node (ref "CI106") (pin "1") (pintype "passive"))
      (node (ref "CI107") (pin "1") (pintype "passive"))
      (node (ref "CI108") (pin "1") (pintype "passive"))
      (node (ref "CI109") (pin "2") (pintype "passive"))
      (node (ref "CI110") (pin "2") (pintype "passive"))
      (node (ref "CI111") (pin "2") (pintype "passive"))
      (node (ref "CI112") (pin "2") (pintype "passive"))
      (node (ref "CI117") (pin "1") (pintype "passive"))
      (node (ref "CI118") (pin "1") (pintype "passive"))
      (node (ref "CI119") (pin "1") (pintype "passive"))
      (node (ref "CI120") (pin "1") (pintype "passive"))
      (node (ref "CI121") (pin "2") (pintype "passive"))
      (node (ref "CI122") (pin "2") (pintype "passive"))
      (node (ref "CI123") (pin "2") (pintype "passive"))
      (node (ref "CI124") (pin "2") (pintype "passive"))
      (node (ref "CI129") (pin "2") (pintype "passive"))
      (node (ref "CI13") (pin "1") (pintype "passive"))
      (node (ref "CI130") (pin "2") (pintype "passive"))
      (node (ref "CI131") (pin "1") (pintype "passive"))
      (node (ref "CI132") (pin "1") (pintype "passive"))
      (node (ref "CI14") (pin "1") (pintype "passive"))
      (node (ref "CI15") (pin "1") (pintype "passive"))
      (node (ref "CI16") (pin "1") (pintype "passive"))
      (node (ref "CI17") (pin "1") (pintype "passive"))
      (node (ref "CI18") (pin "1") (pintype "passive"))
      (node (ref "CI19") (pin "2") (pintype "passive"))
      (node (ref "CI2") (pin "2") (pintype "passive"))
      (node (ref "CI20") (pin "2") (pintype "passive"))
      (node (ref "CI21") (pin "2") (pintype "passive"))
      (node (ref "CI22") (pin "2") (pintype "passive"))
      (node (ref "CI23") (pin "2") (pintype "passive"))
      (node (ref "CI24") (pin "2") (pintype "passive"))
      (node (ref "CI3") (pin "2") (pintype "passive"))
      (node (ref "CI31") (pin "2") (pintype "passive"))
      (node (ref "CI32") (pin "2") (pintype "passive"))
      (node (ref "CI33") (pin "2") (pintype "passive"))
      (node (ref "CI34") (pin "1") (pintype "passive"))
      (node (ref "CI35") (pin "1") (pintype "passive"))
      (node (ref "CI36") (pin "1") (pintype "passive"))
      (node (ref "CI37") (pin "2") (pintype "passive"))
      (node (ref "CI38") (pin "2") (pintype "passive"))
      (node (ref "CI39") (pin "2") (pintype "passive"))
      (node (ref "CI4") (pin "2") (pintype "passive"))
      (node (ref "CI40") (pin "2") (pintype "passive"))
      (node (ref "CI41") (pin "2") (pintype "passive"))
      (node (ref "CI42") (pin "2") (pintype "passive"))
      (node (ref "CI49") (pin "1") (pintype "passive"))
      (node (ref "CI5") (pin "2") (pintype "passive"))
      (node (ref "CI50") (pin "1") (pintype "passive"))
      (node (ref "CI51") (pin "1") (pintype "passive"))
      (node (ref "CI52") (pin "1") (pintype "passive"))
      (node (ref "CI55") (pin "2") (pintype "passive"))
      (node (ref "CI56") (pin "2") (pintype "passive"))
      (node (ref "CI57") (pin "2") (pintype "passive"))
      (node (ref "CI58") (pin "2") (pintype "passive"))
      (node (ref "CI59") (pin "2") (pintype "passive"))
      (node (ref "CI6") (pin "2") (pintype "passive"))
      (node (ref "CI60") (pin "2") (pintype "passive"))
      (node (ref "CI67") (pin "2") (pintype "passive"))
      (node (ref "CI68") (pin "2") (pintype "passive"))
      (node (ref "CI69") (pin "2") (pintype "passive"))
      (node (ref "CI70") (pin "1") (pintype "passive"))
      (node (ref "CI71") (pin "1") (pintype "passive"))
      (node (ref "CI72") (pin "1") (pintype "passive"))
      (node (ref "CI73") (pin "2") (pintype "passive"))
      (node (ref "CI74") (pin "2") (pintype "passive"))
      (node (ref "CI75") (pin "2") (pintype "passive"))
      (node (ref "CI76") (pin "2") (pintype "passive"))
      (node (ref "CI77") (pin "2") (pintype "passive"))
      (node (ref "CI78") (pin "2") (pintype "passive"))
      (node (ref "CI85") (pin "1") (pintype "passive"))
      (node (ref "CI86") (pin "1") (pintype "passive"))
      (node (ref "CI87") (pin "1") (pintype "passive"))
      (node (ref "CI88") (pin "1") (pintype "passive"))
      (node (ref "CI89") (pin "1") (pintype "passive"))
      (node (ref "CI90") (pin "1") (pintype "passive"))
      (node (ref "CI91") (pin "2") (pintype "passive"))
      (node (ref "CI92") (pin "2") (pintype "passive"))
      (node (ref "CI93") (pin "2") (pintype "passive"))
      (node (ref "CI94") (pin "2") (pintype "passive"))
      (node (ref "CI95") (pin "2") (pintype "passive"))
      (node (ref "CI96") (pin "2") (pintype "passive"))
    )
    (net (code "93") (name "Net-(CI53-Pad1)") (class "Default")
      (node (ref "CI53") (pin "1") (pintype "passive"))
      (node (ref "CI54") (pin "1") (pintype "passive"))
    )
    (net (code "94") (name "Net-(UI1-OUT1)") (class "Default")
      (node (ref "CI7") (pin "1") (pintype "passive"))
      (node (ref "RI1") (pin "2") (pintype "passive"))
      (node (ref "RI7") (pin "2") (pintype "passive"))
      (node (ref "UI1") (pin "1") (pinfunction "OUT1_1") (pintype "output"))
    )
    (net (code "95") (name "Net-(UI1-OUT2)") (class "Default")
      (node (ref "CI25") (pin "2") (pintype "passive"))
      (node (ref "RI13") (pin "2") (pintype "passive"))
      (node (ref "RI19") (pin "2") (pintype "passive"))
      (node (ref "UI1") (pin "7") (pinfunction "OUT2_7") (pintype "output"))
    )
    (net (code "96") (name "Net-(UI1-OUT3)") (class "Default")
      (node (ref "CI26") (pin "2") (pintype "passive"))
      (node (ref "RI14") (pin "1") (pintype "passive"))
      (node (ref "RI22") (pin "1") (pintype "passive"))
      (node (ref "UI1") (pin "8") (pinfunction "OUT3_8") (pintype "output"))
    )
    (net (code "97") (name "Net-(UI1-OUT4)") (class "Default")
      (node (ref "CI10") (pin "1") (pintype "passive"))
      (node (ref "RI10") (pin "2") (pintype "passive"))
      (node (ref "RI4") (pin "1") (pintype "passive"))
      (node (ref "UI1") (pin "14") (pinfunction "OUT4_14") (pintype "output"))
    )
    (net (code "98") (name "Net-(UI2-OUT1)") (class "Default")
      (node (ref "CI8") (pin "1") (pintype "passive"))
      (node (ref "RI2") (pin "2") (pintype "passive"))
      (node (ref "RI8") (pin "2") (pintype "passive"))
      (node (ref "UI2") (pin "1") (pinfunction "OUT1_1") (pintype "output"))
    )
    (net (code "99") (name "Net-(UI2-OUT2)") (class "Default")
      (node (ref "CI27") (pin "2") (pintype "passive"))
      (node (ref "RI15") (pin "2") (pintype "passive"))
      (node (ref "RI20") (pin "2") (pintype "passive"))
      (node (ref "UI2") (pin "7") (pinfunction "OUT2_7") (pintype "output"))
    )
    (net (code "100") (name "Net-(UI2-OUT3)") (class "Default")
      (node (ref "CI28") (pin "2") (pintype "passive"))
      (node (ref "RI16") (pin "1") (pintype "passive"))
      (node (ref "RI23") (pin "1") (pintype "passive"))
      (node (ref "UI2") (pin "8") (pinfunction "OUT3_8") (pintype "output"))
    )
    (net (code "101") (name "Net-(UI2-OUT4)") (class "Default")
      (node (ref "CI11") (pin "1") (pintype "passive"))
      (node (ref "RI11") (pin "2") (pintype "passive"))
      (node (ref "RI5") (pin "1") (pintype "passive"))
      (node (ref "UI2") (pin "14") (pinfunction "OUT4_14") (pintype "output"))
    )
    (net (code "102") (name "Net-(UI3-OUT1)") (class "Default")
      (node (ref "CI9") (pin "1") (pintype "passive"))
      (node (ref "RI3") (pin "2") (pintype "passive"))
      (node (ref "RI9") (pin "2") (pintype "passive"))
      (node (ref "UI3") (pin "1") (pinfunction "OUT1_1") (pintype "output"))
    )
    (net (code "103") (name "Net-(UI3-OUT2)") (class "Default")
      (node (ref "CI29") (pin "2") (pintype "passive"))
      (node (ref "RI17") (pin "2") (pintype "passive"))
      (node (ref "RI21") (pin "2") (pintype "passive"))
      (node (ref "UI3") (pin "7") (pinfunction "OUT2_7") (pintype "output"))
    )
    (net (code "104") (name "Net-(UI3-OUT3)") (class "Default")
      (node (ref "CI30") (pin "2") (pintype "passive"))
      (node (ref "RI18") (pin "1") (pintype "passive"))
      (node (ref "RI24") (pin "1") (pintype "passive"))
      (node (ref "UI3") (pin "8") (pinfunction "OUT3_8") (pintype "output"))
    )
    (net (code "105") (name "Net-(UI3-OUT4)") (class "Default")
      (node (ref "CI12") (pin "1") (pintype "passive"))
      (node (ref "RI12") (pin "2") (pintype "passive"))
      (node (ref "RI6") (pin "1") (pintype "passive"))
      (node (ref "UI3") (pin "14") (pinfunction "OUT4_14") (pintype "output"))
    )
    (net (code "106") (name "Net-(UI4-OUT1)") (class "Default")
      (node (ref "CI43") (pin "1") (pintype "passive"))
      (node (ref "RI25") (pin "2") (pintype "passive"))
      (node (ref "RI31") (pin "2") (pintype "passive"))
      (node (ref "UI4") (pin "1") (pinfunction "OUT1_1") (pintype "output"))
    )
    (net (code "107") (name "Net-(UI4-OUT2)") (class "Default")
      (node (ref "CI61") (pin "2") (pintype "passive"))
      (node (ref "RI37") (pin "2") (pintype "passive"))
      (node (ref "RI43") (pin "2") (pintype "passive"))
      (node (ref "UI4") (pin "7") (pinfunction "OUT2_7") (pintype "output"))
    )
    (net (code "108") (name "Net-(UI4-OUT3)") (class "Default")
      (node (ref "CI62") (pin "2") (pintype "passive"))
      (node (ref "RI38") (pin "1") (pintype "passive"))
      (node (ref "RI46") (pin "1") (pintype "passive"))
      (node (ref "UI4") (pin "8") (pinfunction "OUT3_8") (pintype "output"))
    )
    (net (code "109") (name "Net-(UI4-OUT4)") (class "Default")
      (node (ref "CI46") (pin "1") (pintype "passive"))
      (node (ref "RI28") (pin "1") (pintype "passive"))
      (node (ref "RI34") (pin "2") (pintype "passive"))
      (node (ref "UI4") (pin "14") (pinfunction "OUT4_14") (pintype "output"))
    )
    (net (code "110") (name "Net-(UI5-OUT1)") (class "Default")
      (node (ref "CI44") (pin "1") (pintype "passive"))
      (node (ref "RI26") (pin "2") (pintype "passive"))
      (node (ref "RI32") (pin "2") (pintype "passive"))
      (node (ref "UI5") (pin "1") (pinfunction "OUT1_1") (pintype "output"))
    )
    (net (code "111") (name "Net-(UI5-OUT2)") (class "Default")
      (node (ref "CI63") (pin "2") (pintype "passive"))
      (node (ref "RI39") (pin "2") (pintype "passive"))
      (node (ref "RI44") (pin "2") (pintype "passive"))
      (node (ref "UI5") (pin "7") (pinfunction "OUT2_7") (pintype "output"))
    )
    (net (code "112") (name "Net-(UI5-OUT3)") (class "Default")
      (node (ref "CI64") (pin "2") (pintype "passive"))
      (node (ref "RI40") (pin "1") (pintype "passive"))
      (node (ref "RI47") (pin "1") (pintype "passive"))
      (node (ref "UI5") (pin "8") (pinfunction "OUT3_8") (pintype "output"))
    )
    (net (code "113") (name "Net-(UI5-OUT4)") (class "Default")
      (node (ref "CI47") (pin "1") (pintype "passive"))
      (node (ref "RI29") (pin "1") (pintype "passive"))
      (node (ref "RI35") (pin "2") (pintype "passive"))
      (node (ref "UI5") (pin "14") (pinfunction "OUT4_14") (pintype "output"))
    )
    (net (code "114") (name "Net-(UI6-OUT1)") (class "Default")
      (node (ref "CI45") (pin "1") (pintype "passive"))
      (node (ref "RI27") (pin "2") (pintype "passive"))
      (node (ref "RI33") (pin "2") (pintype "passive"))
      (node (ref "UI6") (pin "1") (pinfunction "OUT1_1") (pintype "output"))
    )
    (net (code "115") (name "Net-(UI6-OUT2)") (class "Default")
      (node (ref "CI65") (pin "2") (pintype "passive"))
      (node (ref "RI41") (pin "2") (pintype "passive"))
      (node (ref "RI45") (pin "2") (pintype "passive"))
      (node (ref "UI6") (pin "7") (pinfunction "OUT2_7") (pintype "output"))
    )
    (net (code "116") (name "Net-(UI6-OUT3)") (class "Default")
      (node (ref "CI66") (pin "2") (pintype "passive"))
      (node (ref "RI42") (pin "1") (pintype "passive"))
      (node (ref "RI48") (pin "1") (pintype "passive"))
      (node (ref "UI6") (pin "8") (pinfunction "OUT3_8") (pintype "output"))
    )
    (net (code "117") (name "Net-(UI6-OUT4)") (class "Default")
      (node (ref "CI48") (pin "1") (pintype "passive"))
      (node (ref "RI30") (pin "1") (pintype "passive"))
      (node (ref "RI36") (pin "2") (pintype "passive"))
      (node (ref "UI6") (pin "14") (pinfunction "OUT4_14") (pintype "output"))
    )
    (net (code "118") (name "Net-(UI7-OUT1)") (class "Default")
      (node (ref "CI79") (pin "1") (pintype "passive"))
      (node (ref "RI49") (pin "2") (pintype "passive"))
      (node (ref "RI55") (pin "2") (pintype "passive"))
      (node (ref "UI7") (pin "1") (pinfunction "OUT1_1") (pintype "output"))
    )
    (net (code "119") (name "Net-(UI7-OUT2)") (class "Default")
      (node (ref "CI97") (pin "2") (pintype "passive"))
      (node (ref "RI61") (pin "2") (pintype "passive"))
      (node (ref "RI67") (pin "2") (pintype "passive"))
      (node (ref "UI7") (pin "7") (pinfunction "OUT2_7") (pintype "output"))
    )
    (net (code "120") (name "Net-(UI7-OUT3)") (class "Default")
      (node (ref "CI98") (pin "2") (pintype "passive"))
      (node (ref "RI62") (pin "1") (pintype "passive"))
      (node (ref "RI70") (pin "1") (pintype "passive"))
      (node (ref "UI7") (pin "8") (pinfunction "OUT3_8") (pintype "output"))
    )
    (net (code "121") (name "Net-(UI7-OUT4)") (class "Default")
      (node (ref "CI82") (pin "1") (pintype "passive"))
      (node (ref "RI52") (pin "1") (pintype "passive"))
      (node (ref "RI58") (pin "2") (pintype "passive"))
      (node (ref "UI7") (pin "14") (pinfunction "OUT4_14") (pintype "output"))
    )
    (net (code "122") (name "Net-(UI8-OUT1)") (class "Default")
      (node (ref "CI80") (pin "1") (pintype "passive"))
      (node (ref "RI50") (pin "2") (pintype "passive"))
      (node (ref "RI56") (pin "2") (pintype "passive"))
      (node (ref "UI8") (pin "1") (pinfunction "OUT1_1") (pintype "output"))
    )
    (net (code "123") (name "Net-(UI8-OUT2)") (class "Default")
      (node (ref "CI99") (pin "2") (pintype "passive"))
      (node (ref "RI63") (pin "2") (pintype "passive"))
      (node (ref "RI68") (pin "2") (pintype "passive"))
      (node (ref "UI8") (pin "7") (pinfunction "OUT2_7") (pintype "output"))
    )
    (net (code "124") (name "Net-(UI8-OUT3)") (class "Default")
      (node (ref "CI100") (pin "2") (pintype "passive"))
      (node (ref "RI64") (pin "1") (pintype "passive"))
      (node (ref "RI71") (pin "1") (pintype "passive"))
      (node (ref "UI8") (pin "8") (pinfunction "OUT3_8") (pintype "output"))
    )
    (net (code "125") (name "Net-(UI8-OUT4)") (class "Default")
      (node (ref "CI83") (pin "1") (pintype "passive"))
      (node (ref "RI53") (pin "1") (pintype "passive"))
      (node (ref "RI59") (pin "2") (pintype "passive"))
      (node (ref "UI8") (pin "14") (pinfunction "OUT4_14") (pintype "output"))
    )
    (net (code "126") (name "Net-(UI9-OUT1)") (class "Default")
      (node (ref "CI81") (pin "1") (pintype "passive"))
      (node (ref "RI51") (pin "2") (pintype "passive"))
      (node (ref "RI57") (pin "2") (pintype "passive"))
      (node (ref "UI9") (pin "1") (pinfunction "OUT1_1") (pintype "output"))
    )
    (net (code "127") (name "Net-(UI9-OUT2)") (class "Default")
      (node (ref "CI101") (pin "2") (pintype "passive"))
      (node (ref "RI65") (pin "2") (pintype "passive"))
      (node (ref "RI69") (pin "2") (pintype "passive"))
      (node (ref "UI9") (pin "7") (pinfunction "OUT2_7") (pintype "output"))
    )
    (net (code "128") (name "Net-(UI9-OUT3)") (class "Default")
      (node (ref "CI102") (pin "2") (pintype "passive"))
      (node (ref "RI66") (pin "1") (pintype "passive"))
      (node (ref "RI72") (pin "1") (pintype "passive"))
      (node (ref "UI9") (pin "8") (pinfunction "OUT3_8") (pintype "output"))
    )
    (net (code "129") (name "Net-(UI9-OUT4)") (class "Default")
      (node (ref "CI84") (pin "1") (pintype "passive"))
      (node (ref "RI54") (pin "1") (pintype "passive"))
      (node (ref "RI60") (pin "2") (pintype "passive"))
      (node (ref "UI9") (pin "14") (pinfunction "OUT4_14") (pintype "output"))
    )
    (net (code "130") (name "Net-(UI10-OUT1)") (class "Default")
      (node (ref "CI113") (pin "1") (pintype "passive"))
      (node (ref "RI73") (pin "2") (pintype "passive"))
      (node (ref "RI77") (pin "2") (pintype "passive"))
      (node (ref "UI10") (pin "1") (pinfunction "OUT1_1") (pintype "output"))
    )
    (net (code "131") (name "Net-(UI10-OUT2)") (class "Default")
      (node (ref "CI125") (pin "2") (pintype "passive"))
      (node (ref "RI81") (pin "2") (pintype "passive"))
      (node (ref "RI85") (pin "2") (pintype "passive"))
      (node (ref "UI10") (pin "7") (pinfunction "OUT2_7") (pintype "output"))
    )
    (net (code "132") (name "Net-(UI10-OUT3)") (class "Default")
      (node (ref "CI126") (pin "2") (pintype "passive"))
      (node (ref "RI82") (pin "1") (pintype "passive"))
      (node (ref "RI87") (pin "1") (pintype "passive"))
      (node (ref "UI10") (pin "8") (pinfunction "OUT3_8") (pintype "output"))
    )
    (net (code "133") (name "Net-(UI10-OUT4)") (class "Default")
      (node (ref "CI115") (pin "1") (pintype "passive"))
      (node (ref "RI75") (pin "1") (pintype "passive"))
      (node (ref "RI79") (pin "2") (pintype "passive"))
      (node (ref "UI10") (pin "14") (pinfunction "OUT4_14") (pintype "output"))
    )
    (net (code "134") (name "Net-(UI11-OUT1)") (class "Default")
      (node (ref "CI114") (pin "1") (pintype "passive"))
      (node (ref "RI74") (pin "2") (pintype "passive"))
      (node (ref "RI78") (pin "2") (pintype "passive"))
      (node (ref "UI11") (pin "1") (pinfunction "OUT1_1") (pintype "output"))
    )
    (net (code "135") (name "Net-(UI11-OUT2)") (class "Default")
      (node (ref "CI127") (pin "2") (pintype "passive"))
      (node (ref "RI83") (pin "2") (pintype "passive"))
      (node (ref "RI86") (pin "2") (pintype "passive"))
      (node (ref "UI11") (pin "7") (pinfunction "OUT2_7") (pintype "output"))
    )
    (net (code "136") (name "Net-(UI11-OUT3)") (class "Default")
      (node (ref "CI128") (pin "2") (pintype "passive"))
      (node (ref "RI84") (pin "1") (pintype "passive"))
      (node (ref "RI88") (pin "1") (pintype "passive"))
      (node (ref "UI11") (pin "8") (pinfunction "OUT3_8") (pintype "output"))
    )
    (net (code "137") (name "Net-(UI11-OUT4)") (class "Default")
      (node (ref "CI116") (pin "1") (pintype "passive"))
      (node (ref "RI76") (pin "1") (pintype "passive"))
      (node (ref "RI80") (pin "2") (pintype "passive"))
      (node (ref "UI11") (pin "14") (pinfunction "OUT4_14") (pintype "output"))
    )
  )
)
